# Nixie_3757b.net
KiCad netlist of a schematic drawn in EAGLE
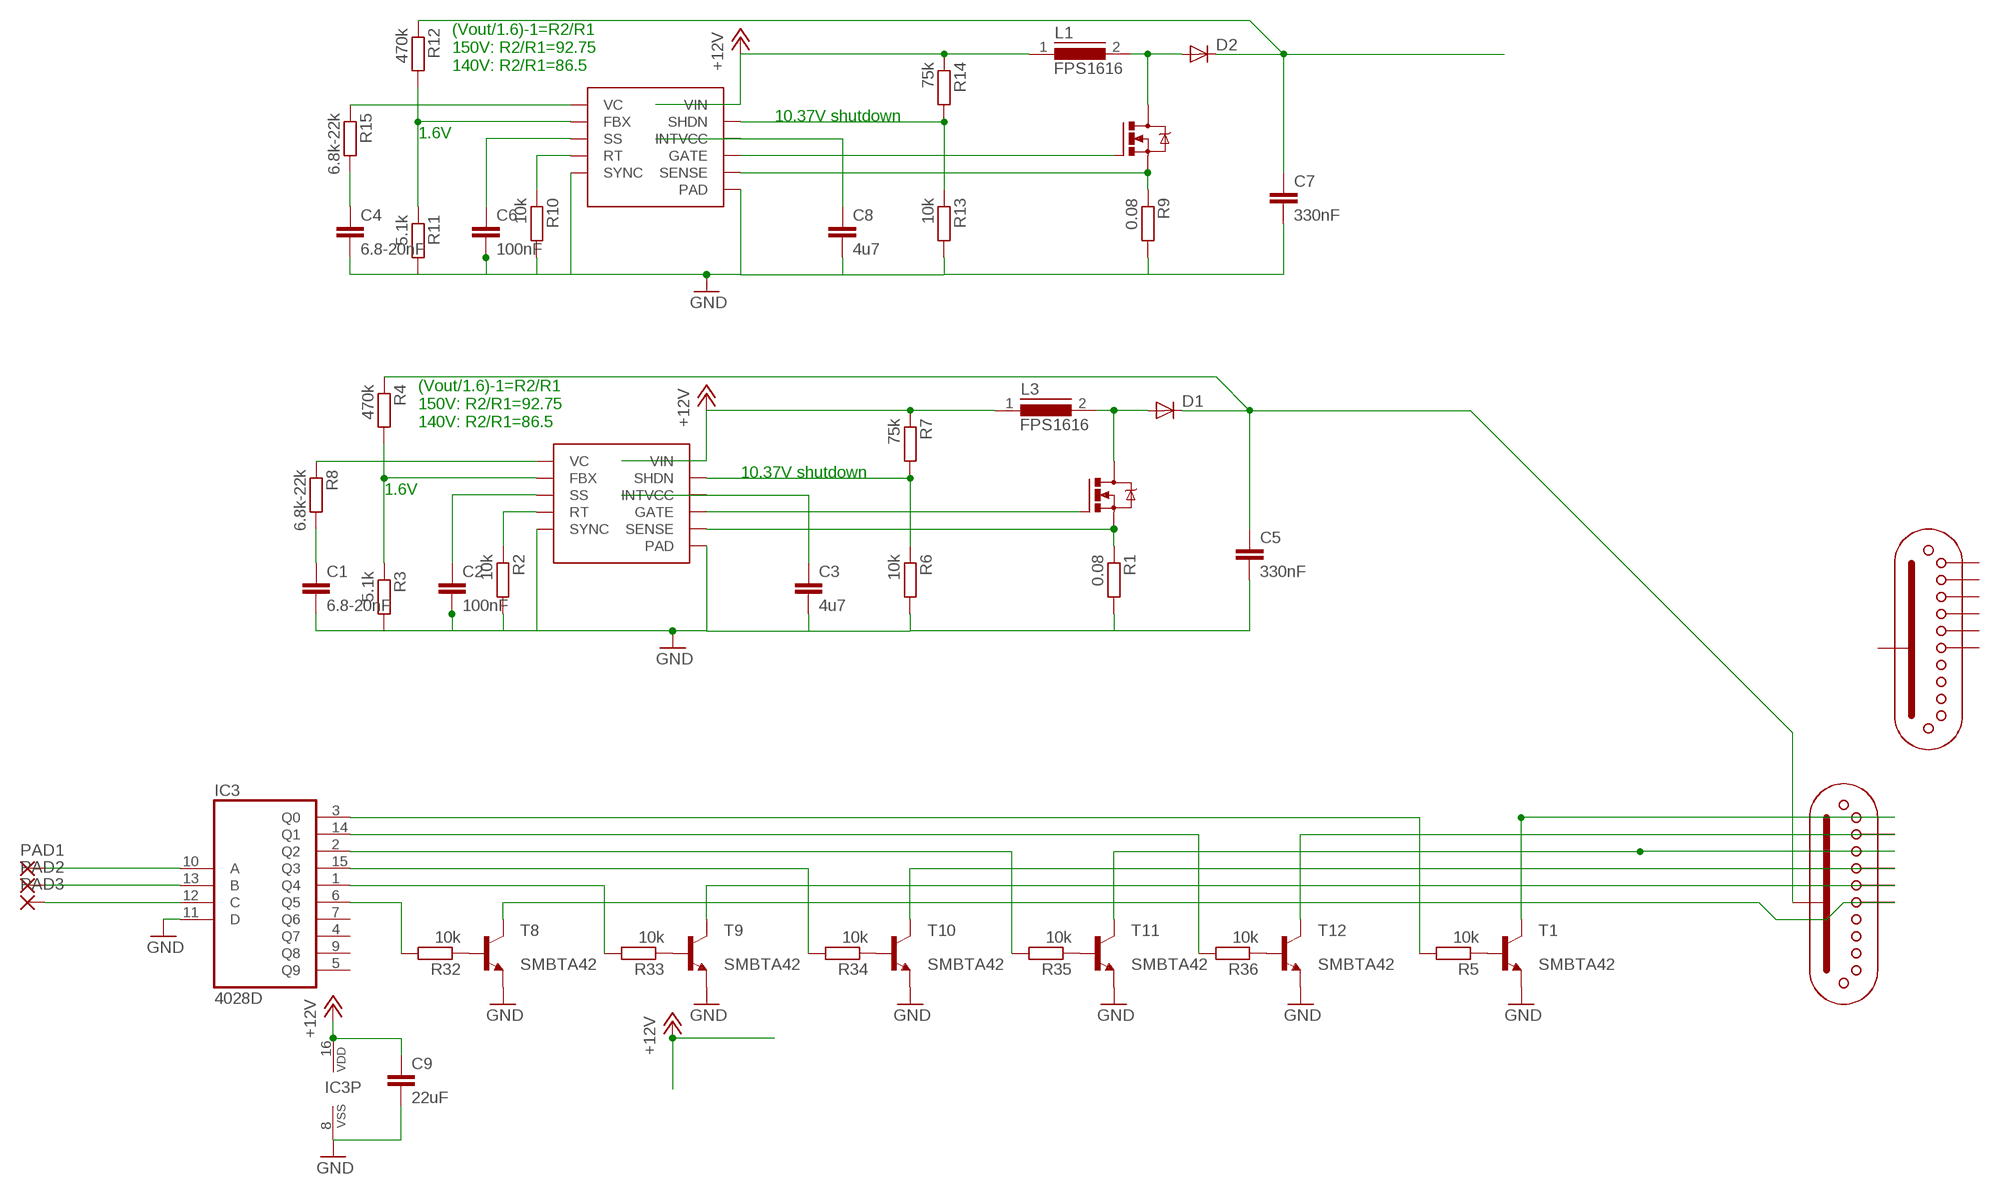
[diagram p0: schematic, sheet 1]

(export (version "E")
  (design (tool "Eeschema 10.0.6"))
  (components
    (comp (ref "C1")
      (value "6.8-20nF")
      (footprint "eagle-import:C0805K")
      (libsource (lib "eagle-import") (part "C-EUC0805K"))
    )
    (comp (ref "C2")
      (value "100nF")
      (footprint "eagle-import:C0805K")
      (libsource (lib "eagle-import") (part "C-EUC0805K"))
    )
    (comp (ref "C3")
      (value "4u7")
      (footprint "eagle-import:C0805K")
      (libsource (lib "eagle-import") (part "C-EUC0805K"))
    )
    (comp (ref "C4")
      (value "6.8-20nF")
      (footprint "eagle-import:C0805K")
      (libsource (lib "eagle-import") (part "C-EUC0805K"))
    )
    (comp (ref "C5")
      (value "330nF")
      (footprint "eagle-import:C1812")
      (libsource (lib "eagle-import") (part "C-EUC1812"))
    )
    (comp (ref "C6")
      (value "100nF")
      (footprint "eagle-import:C0805K")
      (libsource (lib "eagle-import") (part "C-EUC0805K"))
    )
    (comp (ref "C7")
      (value "330nF")
      (footprint "eagle-import:C1812")
      (libsource (lib "eagle-import") (part "C-EUC1812"))
    )
    (comp (ref "C8")
      (value "4u7")
      (footprint "eagle-import:C0805K")
      (libsource (lib "eagle-import") (part "C-EUC0805K"))
    )
    (comp (ref "C9")
      (value "22uF")
      (footprint "eagle-import:C1210K")
      (libsource (lib "eagle-import") (part "C-EUC1210K"))
    )
    (comp (ref "D1")
      (value "DIODE-DO219AB")
      (footprint "eagle-import:DO219AB")
      (libsource (lib "eagle-import") (part "DIODE-DO219AB"))
    )
    (comp (ref "D2")
      (value "DIODE-DO219AB")
      (footprint "eagle-import:DO219AB")
      (libsource (lib "eagle-import") (part "DIODE-DO219AB"))
    )
    (comp (ref "IC3")
      (value "4028D")
      (footprint "eagle-import:SO16")
      (libsource (lib "eagle-import") (part "4028D"))
    )
    (comp (ref "L1")
      (value "FPS1616")
      (footprint "eagle-import:1616FPS_22UH")
      (libsource (lib "eagle-import") (part "FPS1616"))
    )
    (comp (ref "L3")
      (value "FPS1616")
      (footprint "eagle-import:1616FPS_22UH")
      (libsource (lib "eagle-import") (part "FPS1616"))
    )
    (comp (ref "PAD1")
      (value "1,6/0,8")
      (footprint "eagle-import:1,6_0,8")
      (libsource (lib "eagle-import") (part "1,6/0,8"))
    )
    (comp (ref "PAD2")
      (value "1,6/0,8")
      (footprint "eagle-import:1,6_0,8")
      (libsource (lib "eagle-import") (part "1,6/0,8"))
    )
    (comp (ref "PAD3")
      (value "1,6/0,8")
      (footprint "eagle-import:1,6_0,8")
      (libsource (lib "eagle-import") (part "1,6/0,8"))
    )
    (comp (ref "Q1")
      (value "N-MOSFET-TO252-DPAK")
      (footprint "eagle-import:TO252")
      (libsource (lib "eagle-import") (part "N-MOSFET-TO252-DPAK"))
    )
    (comp (ref "Q4")
      (value "N-MOSFET-TO252-DPAK")
      (footprint "eagle-import:TO252")
      (libsource (lib "eagle-import") (part "N-MOSFET-TO252-DPAK"))
    )
    (comp (ref "R1")
      (value "0.08")
      (footprint "eagle-import:R0805")
      (libsource (lib "eagle-import") (part "R-EU_R0805"))
    )
    (comp (ref "R2")
      (value "10k")
      (footprint "eagle-import:R0805")
      (libsource (lib "eagle-import") (part "R-EU_R0805"))
    )
    (comp (ref "R3")
      (value "5.1k")
      (footprint "eagle-import:R0805")
      (libsource (lib "eagle-import") (part "R-EU_R0805"))
    )
    (comp (ref "R4")
      (value "470k")
      (footprint "eagle-import:R0805")
      (libsource (lib "eagle-import") (part "R-EU_R0805"))
    )
    (comp (ref "R5")
      (value "10k")
      (footprint "eagle-import:R0805")
      (libsource (lib "eagle-import") (part "R-EU_R0805"))
    )
    (comp (ref "R6")
      (value "10k")
      (footprint "eagle-import:R0805")
      (libsource (lib "eagle-import") (part "R-EU_R0805"))
    )
    (comp (ref "R7")
      (value "75k")
      (footprint "eagle-import:R0805")
      (libsource (lib "eagle-import") (part "R-EU_R0805"))
    )
    (comp (ref "R8")
      (value "6.8k-22k")
      (footprint "eagle-import:R0805")
      (libsource (lib "eagle-import") (part "R-EU_R0805"))
    )
    (comp (ref "R9")
      (value "0.08")
      (footprint "eagle-import:R0805")
      (libsource (lib "eagle-import") (part "R-EU_R0805"))
    )
    (comp (ref "R10")
      (value "10k")
      (footprint "eagle-import:R0805")
      (libsource (lib "eagle-import") (part "R-EU_R0805"))
    )
    (comp (ref "R11")
      (value "5.1k")
      (footprint "eagle-import:R0805")
      (libsource (lib "eagle-import") (part "R-EU_R0805"))
    )
    (comp (ref "R12")
      (value "470k")
      (footprint "eagle-import:R0805")
      (libsource (lib "eagle-import") (part "R-EU_R0805"))
    )
    (comp (ref "R13")
      (value "10k")
      (footprint "eagle-import:R0805")
      (libsource (lib "eagle-import") (part "R-EU_R0805"))
    )
    (comp (ref "R14")
      (value "75k")
      (footprint "eagle-import:R0805")
      (libsource (lib "eagle-import") (part "R-EU_R0805"))
    )
    (comp (ref "R15")
      (value "6.8k-22k")
      (footprint "eagle-import:R0805")
      (libsource (lib "eagle-import") (part "R-EU_R0805"))
    )
    (comp (ref "R32")
      (value "10k")
      (footprint "eagle-import:R0805")
      (libsource (lib "eagle-import") (part "R-EU_R0805"))
    )
    (comp (ref "R33")
      (value "10k")
      (footprint "eagle-import:R0805")
      (libsource (lib "eagle-import") (part "R-EU_R0805"))
    )
    (comp (ref "R34")
      (value "10k")
      (footprint "eagle-import:R0805")
      (libsource (lib "eagle-import") (part "R-EU_R0805"))
    )
    (comp (ref "R35")
      (value "10k")
      (footprint "eagle-import:R0805")
      (libsource (lib "eagle-import") (part "R-EU_R0805"))
    )
    (comp (ref "R36")
      (value "10k")
      (footprint "eagle-import:R0805")
      (libsource (lib "eagle-import") (part "R-EU_R0805"))
    )
    (comp (ref "T1")
      (value "MMBTA42LT1-NPN-SOT23-BEC")
      (footprint "eagle-import:SOT23-BEC")
      (fields (field (name "T") "SMBTA42"))
      (libsource (lib "eagle-import") (part "-NPN-SOT23-BECMMBTA42LT1"))
    )
    (comp (ref "T8")
      (value "MMBTA42LT1-NPN-SOT23-BEC")
      (footprint "eagle-import:SOT23-BEC")
      (fields (field (name "T") "SMBTA42"))
      (libsource (lib "eagle-import") (part "-NPN-SOT23-BECMMBTA42LT1"))
    )
    (comp (ref "T9")
      (value "MMBTA42LT1-NPN-SOT23-BEC")
      (footprint "eagle-import:SOT23-BEC")
      (fields (field (name "T") "SMBTA42"))
      (libsource (lib "eagle-import") (part "-NPN-SOT23-BECMMBTA42LT1"))
    )
    (comp (ref "T10")
      (value "MMBTA42LT1-NPN-SOT23-BEC")
      (footprint "eagle-import:SOT23-BEC")
      (fields (field (name "T") "SMBTA42"))
      (libsource (lib "eagle-import") (part "-NPN-SOT23-BECMMBTA42LT1"))
    )
    (comp (ref "T11")
      (value "MMBTA42LT1-NPN-SOT23-BEC")
      (footprint "eagle-import:SOT23-BEC")
      (fields (field (name "T") "SMBTA42"))
      (libsource (lib "eagle-import") (part "-NPN-SOT23-BECMMBTA42LT1"))
    )
    (comp (ref "T12")
      (value "MMBTA42LT1-NPN-SOT23-BEC")
      (footprint "eagle-import:SOT23-BEC")
      (fields (field (name "T") "SMBTA42"))
      (libsource (lib "eagle-import") (part "-NPN-SOT23-BECMMBTA42LT1"))
    )
    (comp (ref "U$1")
      (value "ZM1020")
      (footprint "eagle-import:ZM1020")
      (libsource (lib "eagle-import") (part "ZM1020"))
    )
    (comp (ref "U$3")
      (value "ZM1020")
      (footprint "eagle-import:ZM1020")
      (libsource (lib "eagle-import") (part "ZM1020"))
    )
    (comp (ref "U1")
      (value "LT3757MSOP-10")
      (footprint "eagle-import:MSOP-10")
      (libsource (lib "eagle-import") (part "LT3757MSOP-10"))
    )
    (comp (ref "U2")
      (value "LT3757MSOP-10")
      (footprint "eagle-import:MSOP-10")
      (libsource (lib "eagle-import") (part "LT3757MSOP-10"))
    )
  )
  (nets
    (net (code "1") (name "+12V") (class "Default")
      (node (ref "C9") (pin "1") (pinfunction "1_1") (pintype "passive"))
      (node (ref "IC3") (pin "16") (pinfunction "VDD_16") (pintype "power_in"))
      (node (ref "L1") (pin "1") (pinfunction "1_1") (pintype "passive"))
      (node (ref "L3") (pin "1") (pinfunction "1_1") (pintype "passive"))
      (node (ref "R14") (pin "1") (pinfunction "1_1") (pintype "passive"))
      (node (ref "R7") (pin "1") (pinfunction "1_1") (pintype "passive"))
      (node (ref "U1") (pin "10") (pinfunction "VIN_10") (pintype "bidirectional"))
      (node (ref "U2") (pin "10") (pinfunction "VIN_10") (pintype "bidirectional"))
    )
    (net (code "2") (name "GND") (class "Default")
      (node (ref "C1") (pin "2") (pinfunction "2_2") (pintype "passive"))
      (node (ref "C2") (pin "2") (pinfunction "2_2") (pintype "passive"))
      (node (ref "C3") (pin "2") (pinfunction "2_2") (pintype "passive"))
      (node (ref "C4") (pin "2") (pinfunction "2_2") (pintype "passive"))
      (node (ref "C5") (pin "2") (pinfunction "2_2") (pintype "passive"))
      (node (ref "C6") (pin "2") (pinfunction "2_2") (pintype "passive"))
      (node (ref "C7") (pin "2") (pinfunction "2_2") (pintype "passive"))
      (node (ref "C8") (pin "2") (pinfunction "2_2") (pintype "passive"))
      (node (ref "C9") (pin "2") (pinfunction "2_2") (pintype "passive"))
      (node (ref "IC3") (pin "11") (pinfunction "D_11") (pintype "input"))
      (node (ref "IC3") (pin "8") (pinfunction "VSS_8") (pintype "power_in"))
      (node (ref "R1") (pin "2") (pinfunction "2_2") (pintype "passive"))
      (node (ref "R10") (pin "2") (pinfunction "2_2") (pintype "passive"))
      (node (ref "R11") (pin "2") (pinfunction "2_2") (pintype "passive"))
      (node (ref "R13") (pin "2") (pinfunction "2_2") (pintype "passive"))
      (node (ref "R2") (pin "2") (pinfunction "2_2") (pintype "passive"))
      (node (ref "R3") (pin "2") (pinfunction "2_2") (pintype "passive"))
      (node (ref "R6") (pin "2") (pinfunction "2_2") (pintype "passive"))
      (node (ref "R9") (pin "2") (pinfunction "2_2") (pintype "passive"))
      (node (ref "T1") (pin "E") (pinfunction "E_E") (pintype "passive"))
      (node (ref "T10") (pin "E") (pinfunction "E_E") (pintype "passive"))
      (node (ref "T11") (pin "E") (pinfunction "E_E") (pintype "passive"))
      (node (ref "T12") (pin "E") (pinfunction "E_E") (pintype "passive"))
      (node (ref "T8") (pin "E") (pinfunction "E_E") (pintype "passive"))
      (node (ref "T9") (pin "E") (pinfunction "E_E") (pintype "passive"))
      (node (ref "U1") (pin "5") (pinfunction "SYNC_5") (pintype "bidirectional"))
      (node (ref "U1") (pin "PAD") (pinfunction "PAD_PAD") (pintype "bidirectional"))
      (node (ref "U2") (pin "5") (pinfunction "SYNC_5") (pintype "bidirectional"))
      (node (ref "U2") (pin "PAD") (pinfunction "PAD_PAD") (pintype "bidirectional"))
    )
    (net (code "3") (name "Net-(C1-Pad1)") (class "Default")
      (node (ref "C1") (pin "1") (pinfunction "1_1") (pintype "passive"))
      (node (ref "R8") (pin "2") (pinfunction "2_2") (pintype "passive"))
    )
    (net (code "4") (name "Net-(C4-Pad1)") (class "Default")
      (node (ref "C4") (pin "1") (pinfunction "1_1") (pintype "passive"))
      (node (ref "R15") (pin "2") (pinfunction "2_2") (pintype "passive"))
    )
    (net (code "5") (name "Net-(C7-Pad1)") (class "Default")
      (node (ref "C7") (pin "1") (pinfunction "1_1") (pintype "passive"))
      (node (ref "D2") (pin "C") (pinfunction "C_C") (pintype "passive"))
      (node (ref "R12") (pin "1") (pinfunction "1_1") (pintype "passive"))
    )
    (net (code "6") (name "Net-(IC3A-A)") (class "Default")
      (node (ref "IC3") (pin "10") (pinfunction "A_10") (pintype "input"))
      (node (ref "PAD1") (pin "1") (pinfunction "P_1") (pintype "passive"))
    )
    (net (code "7") (name "Net-(IC3A-B)") (class "Default")
      (node (ref "IC3") (pin "13") (pinfunction "B_13") (pintype "input"))
      (node (ref "PAD2") (pin "1") (pinfunction "P_1") (pintype "passive"))
    )
    (net (code "8") (name "Net-(IC3A-C)") (class "Default")
      (node (ref "IC3") (pin "12") (pinfunction "C_12") (pintype "input"))
      (node (ref "PAD3") (pin "1") (pinfunction "P_1") (pintype "passive"))
    )
    (net (code "9") (name "Net-(IC3A-Q0)") (class "Default")
      (node (ref "IC3") (pin "3") (pinfunction "Q0_3") (pintype "output"))
      (node (ref "R5") (pin "2") (pinfunction "2_2") (pintype "passive"))
    )
    (net (code "10") (name "Net-(IC3A-Q1)") (class "Default")
      (node (ref "IC3") (pin "14") (pinfunction "Q1_14") (pintype "output"))
      (node (ref "R36") (pin "2") (pinfunction "2_2") (pintype "passive"))
    )
    (net (code "11") (name "Net-(IC3A-Q2)") (class "Default")
      (node (ref "IC3") (pin "2") (pinfunction "Q2_2") (pintype "output"))
      (node (ref "R35") (pin "2") (pinfunction "2_2") (pintype "passive"))
    )
    (net (code "12") (name "Net-(IC3A-Q3)") (class "Default")
      (node (ref "IC3") (pin "15") (pinfunction "Q3_15") (pintype "output"))
      (node (ref "R34") (pin "2") (pinfunction "2_2") (pintype "passive"))
    )
    (net (code "13") (name "Net-(IC3A-Q4)") (class "Default")
      (node (ref "IC3") (pin "1") (pinfunction "Q4_1") (pintype "output"))
      (node (ref "R33") (pin "2") (pinfunction "2_2") (pintype "passive"))
    )
    (net (code "14") (name "Net-(IC3A-Q5)") (class "Default")
      (node (ref "IC3") (pin "6") (pinfunction "Q5_6") (pintype "output"))
      (node (ref "R32") (pin "2") (pinfunction "2_2") (pintype "passive"))
    )
    (net (code "15") (name "Net-(Q1-D)") (class "Default")
      (node (ref "D2") (pin "A") (pinfunction "A_A") (pintype "passive"))
      (node (ref "L1") (pin "2") (pinfunction "2_2") (pintype "passive"))
      (node (ref "Q1") (pin "3") (pinfunction "D_3") (pintype "passive"))
    )
    (net (code "16") (name "Net-(Q1-G)") (class "Default")
      (node (ref "Q1") (pin "1") (pinfunction "G_1") (pintype "passive"))
      (node (ref "U2") (pin "7") (pinfunction "GATE_7") (pintype "bidirectional"))
    )
    (net (code "17") (name "Net-(Q1-S)") (class "Default")
      (node (ref "Q1") (pin "2") (pinfunction "S_2") (pintype "passive"))
      (node (ref "R9") (pin "1") (pinfunction "1_1") (pintype "passive"))
      (node (ref "U2") (pin "6") (pinfunction "SENSE_6") (pintype "bidirectional"))
    )
    (net (code "18") (name "Net-(Q4-D)") (class "Default")
      (node (ref "D1") (pin "A") (pinfunction "A_A") (pintype "passive"))
      (node (ref "L3") (pin "2") (pinfunction "2_2") (pintype "passive"))
      (node (ref "Q4") (pin "3") (pinfunction "D_3") (pintype "passive"))
    )
    (net (code "19") (name "Net-(Q4-G)") (class "Default")
      (node (ref "Q4") (pin "1") (pinfunction "G_1") (pintype "passive"))
      (node (ref "U1") (pin "7") (pinfunction "GATE_7") (pintype "bidirectional"))
    )
    (net (code "20") (name "Net-(Q4-S)") (class "Default")
      (node (ref "Q4") (pin "2") (pinfunction "S_2") (pintype "passive"))
      (node (ref "R1") (pin "1") (pinfunction "1_1") (pintype "passive"))
      (node (ref "U1") (pin "6") (pinfunction "SENSE_6") (pintype "bidirectional"))
    )
    (net (code "21") (name "Net-(R5-Pad1)") (class "Default")
      (node (ref "R5") (pin "1") (pinfunction "1_1") (pintype "passive"))
      (node (ref "T1") (pin "B") (pinfunction "B_B") (pintype "passive"))
    )
    (net (code "22") (name "Net-(R32-Pad1)") (class "Default")
      (node (ref "R32") (pin "1") (pinfunction "1_1") (pintype "passive"))
      (node (ref "T8") (pin "B") (pinfunction "B_B") (pintype "passive"))
    )
    (net (code "23") (name "Net-(R33-Pad1)") (class "Default")
      (node (ref "R33") (pin "1") (pinfunction "1_1") (pintype "passive"))
      (node (ref "T9") (pin "B") (pinfunction "B_B") (pintype "passive"))
    )
    (net (code "24") (name "Net-(R34-Pad1)") (class "Default")
      (node (ref "R34") (pin "1") (pinfunction "1_1") (pintype "passive"))
      (node (ref "T10") (pin "B") (pinfunction "B_B") (pintype "passive"))
    )
    (net (code "25") (name "Net-(R35-Pad1)") (class "Default")
      (node (ref "R35") (pin "1") (pinfunction "1_1") (pintype "passive"))
      (node (ref "T11") (pin "B") (pinfunction "B_B") (pintype "passive"))
    )
    (net (code "26") (name "Net-(R36-Pad1)") (class "Default")
      (node (ref "R36") (pin "1") (pinfunction "1_1") (pintype "passive"))
      (node (ref "T12") (pin "B") (pinfunction "B_B") (pintype "passive"))
    )
    (net (code "27") (name "Net-(T8-PadC)") (class "Default")
      (node (ref "T8") (pin "C") (pinfunction "C_C") (pintype "passive"))
      (node (ref "U$1") (pin "5") (pinfunction "5_5") (pintype "bidirectional"))
    )
    (net (code "28") (name "Net-(T9-PadC)") (class "Default")
      (node (ref "T9") (pin "C") (pinfunction "C_C") (pintype "passive"))
      (node (ref "U$1") (pin "4") (pinfunction "4_4") (pintype "bidirectional"))
    )
    (net (code "29") (name "Net-(T10-PadC)") (class "Default")
      (node (ref "T10") (pin "C") (pinfunction "C_C") (pintype "passive"))
      (node (ref "U$1") (pin "3") (pinfunction "3_3") (pintype "bidirectional"))
    )
    (net (code "30") (name "Net-(T11-PadC)") (class "Default")
      (node (ref "T11") (pin "C") (pinfunction "C_C") (pintype "passive"))
      (node (ref "U$1") (pin "2") (pinfunction "2_2") (pintype "bidirectional"))
    )
    (net (code "31") (name "Net-(T12-PadC)") (class "Default")
      (node (ref "T12") (pin "C") (pinfunction "C_C") (pintype "passive"))
      (node (ref "U$1") (pin "1") (pinfunction "1_1") (pintype "bidirectional"))
    )
    (net (code "32") (name "Net-(U$1-0)") (class "Default")
      (node (ref "T1") (pin "C") (pinfunction "C_C") (pintype "passive"))
      (node (ref "U$1") (pin "11") (pinfunction "0_11") (pintype "bidirectional"))
    )
    (net (code "33") (name "Net-(U$1-A)") (class "Default")
      (node (ref "C5") (pin "1") (pinfunction "1_1") (pintype "passive"))
      (node (ref "D1") (pin "C") (pinfunction "C_C") (pintype "passive"))
      (node (ref "R4") (pin "1") (pinfunction "1_1") (pintype "passive"))
      (node (ref "U$1") (pin "12") (pinfunction "A_12") (pintype "bidirectional"))
    )
    (net (code "34") (name "Net-(U1-FBX)") (class "Default")
      (node (ref "R3") (pin "1") (pinfunction "1_1") (pintype "passive"))
      (node (ref "R4") (pin "2") (pinfunction "2_2") (pintype "passive"))
      (node (ref "U1") (pin "2") (pinfunction "FBX_2") (pintype "bidirectional"))
    )
    (net (code "35") (name "Net-(U1-INTVCC)") (class "Default")
      (node (ref "C3") (pin "1") (pinfunction "1_1") (pintype "passive"))
      (node (ref "U1") (pin "8") (pinfunction "INTVCC_8") (pintype "bidirectional"))
    )
    (net (code "36") (name "Net-(U1-RT)") (class "Default")
      (node (ref "R2") (pin "1") (pinfunction "1_1") (pintype "passive"))
      (node (ref "U1") (pin "4") (pinfunction "RT_4") (pintype "bidirectional"))
    )
    (net (code "37") (name "Net-(U1-SHDN)") (class "Default")
      (node (ref "R6") (pin "1") (pinfunction "1_1") (pintype "passive"))
      (node (ref "R7") (pin "2") (pinfunction "2_2") (pintype "passive"))
      (node (ref "U1") (pin "9") (pinfunction "SHDN_9") (pintype "bidirectional"))
    )
    (net (code "38") (name "Net-(U1-SS)") (class "Default")
      (node (ref "C2") (pin "1") (pinfunction "1_1") (pintype "passive"))
      (node (ref "U1") (pin "3") (pinfunction "SS_3") (pintype "bidirectional"))
    )
    (net (code "39") (name "Net-(U1-VC)") (class "Default")
      (node (ref "R8") (pin "1") (pinfunction "1_1") (pintype "passive"))
      (node (ref "U1") (pin "1") (pinfunction "VC_1") (pintype "bidirectional"))
    )
    (net (code "40") (name "Net-(U2-FBX)") (class "Default")
      (node (ref "R11") (pin "1") (pinfunction "1_1") (pintype "passive"))
      (node (ref "R12") (pin "2") (pinfunction "2_2") (pintype "passive"))
      (node (ref "U2") (pin "2") (pinfunction "FBX_2") (pintype "bidirectional"))
    )
    (net (code "41") (name "Net-(U2-INTVCC)") (class "Default")
      (node (ref "C8") (pin "1") (pinfunction "1_1") (pintype "passive"))
      (node (ref "U2") (pin "8") (pinfunction "INTVCC_8") (pintype "bidirectional"))
    )
    (net (code "42") (name "Net-(U2-RT)") (class "Default")
      (node (ref "R10") (pin "1") (pinfunction "1_1") (pintype "passive"))
      (node (ref "U2") (pin "4") (pinfunction "RT_4") (pintype "bidirectional"))
    )
    (net (code "43") (name "Net-(U2-SHDN)") (class "Default")
      (node (ref "R13") (pin "1") (pinfunction "1_1") (pintype "passive"))
      (node (ref "R14") (pin "2") (pinfunction "2_2") (pintype "passive"))
      (node (ref "U2") (pin "9") (pinfunction "SHDN_9") (pintype "bidirectional"))
    )
    (net (code "44") (name "Net-(U2-SS)") (class "Default")
      (node (ref "C6") (pin "1") (pinfunction "1_1") (pintype "passive"))
      (node (ref "U2") (pin "3") (pinfunction "SS_3") (pintype "bidirectional"))
    )
    (net (code "45") (name "Net-(U2-VC)") (class "Default")
      (node (ref "R15") (pin "1") (pinfunction "1_1") (pintype "passive"))
      (node (ref "U2") (pin "1") (pinfunction "VC_1") (pintype "bidirectional"))
    )
    (net (code "46") (name "unconnected-(IC3A-Q6-Pad7)") (class "Default")
      (node (ref "IC3") (pin "7") (pinfunction "Q6_7") (pintype "output"))
    )
    (net (code "47") (name "unconnected-(IC3A-Q7-Pad4)") (class "Default")
      (node (ref "IC3") (pin "4") (pinfunction "Q7_4") (pintype "output"))
    )
    (net (code "48") (name "unconnected-(IC3A-Q8-Pad9)") (class "Default")
      (node (ref "IC3") (pin "9") (pinfunction "Q8_9") (pintype "output"))
    )
    (net (code "49") (name "unconnected-(IC3A-Q9-Pad5)") (class "Default")
      (node (ref "IC3") (pin "5") (pinfunction "Q9_5") (pintype "output"))
    )
    (net (code "50") (name "unconnected-(U$3-0-Pad11)") (class "Default")
      (node (ref "U$3") (pin "11") (pinfunction "0_11") (pintype "bidirectional"))
    )
    (net (code "51") (name "unconnected-(U$3-A-Pad12)") (class "Default")
      (node (ref "U$3") (pin "12") (pinfunction "A_12") (pintype "bidirectional"))
    )
    (net (code "52") (name "unconnected-(U$3-Pad1)") (class "Default")
      (node (ref "U$3") (pin "1") (pinfunction "1_1") (pintype "bidirectional"))
    )
    (net (code "53") (name "unconnected-(U$3-Pad2)") (class "Default")
      (node (ref "U$3") (pin "2") (pinfunction "2_2") (pintype "bidirectional"))
    )
    (net (code "54") (name "unconnected-(U$3-Pad3)") (class "Default")
      (node (ref "U$3") (pin "3") (pinfunction "3_3") (pintype "bidirectional"))
    )
    (net (code "55") (name "unconnected-(U$3-Pad4)") (class "Default")
      (node (ref "U$3") (pin "4") (pinfunction "4_4") (pintype "bidirectional"))
    )
    (net (code "56") (name "unconnected-(U$3-Pad5)") (class "Default")
      (node (ref "U$3") (pin "5") (pinfunction "5_5") (pintype "bidirectional"))
    )
  )
)
